# h2.net
KiCad netlist of a schematic drawn in EAGLE
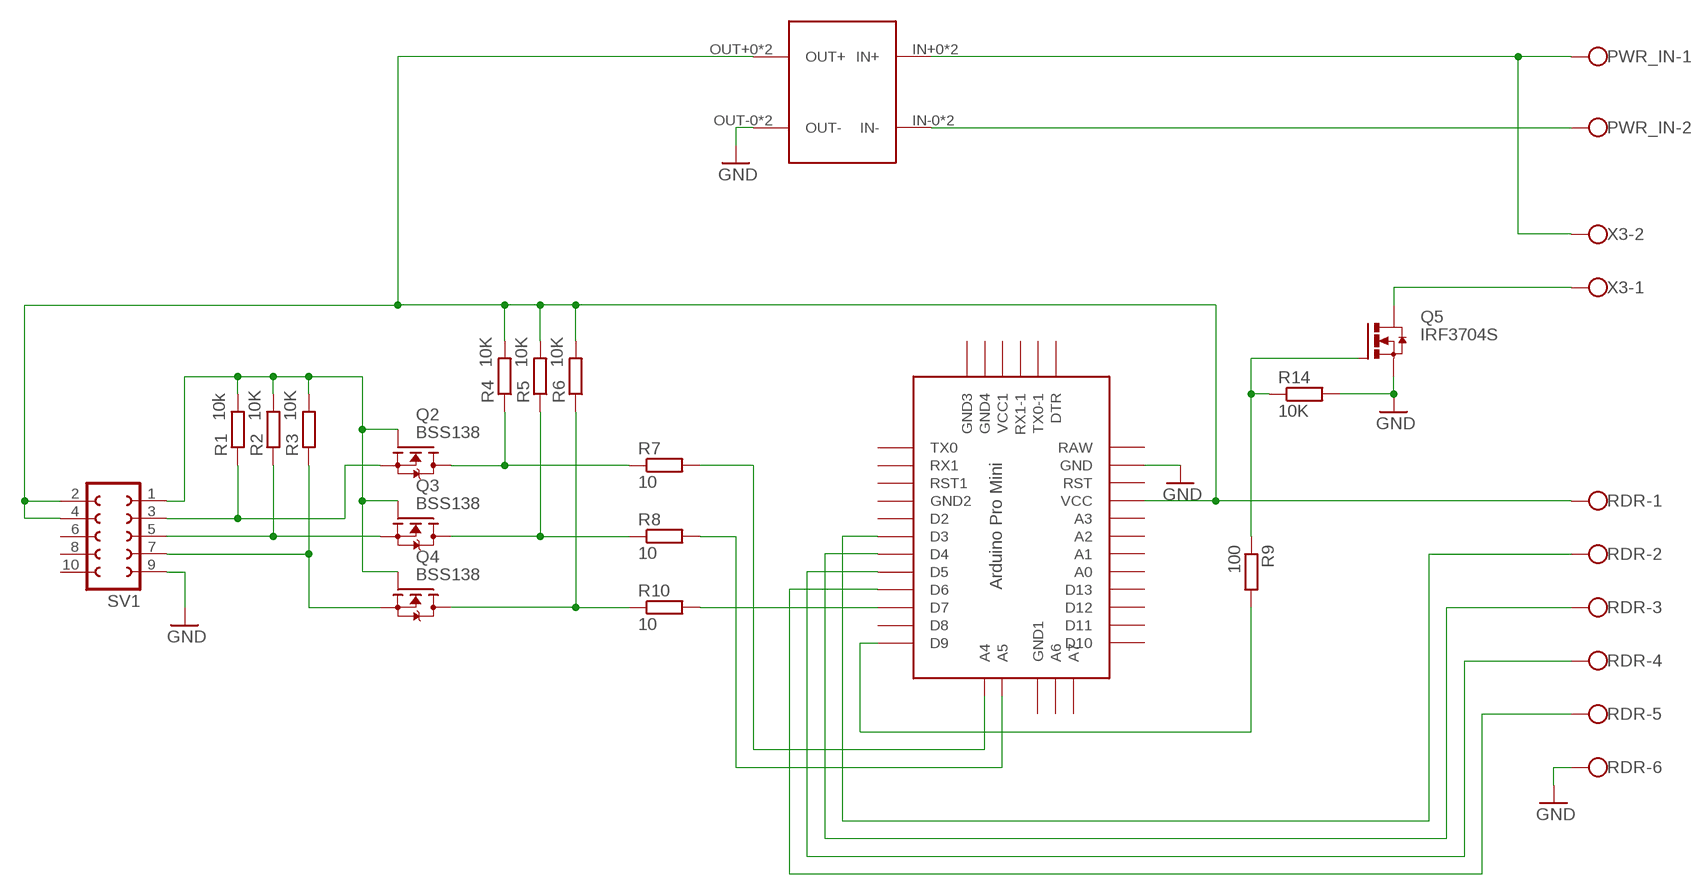
[diagram p0: schematic, sheet 1]

(export (version "E")
  (design (tool "Eeschema 10.0.6"))
  (components
    (comp (ref "PWR_IN")
      (value "W237-102")
      (footprint "eagle-import:W237-102")
      (fields (field (name "MPN") "237-102"))
      (libsource (lib "eagle-import") (part "W237-102"))
    )
    (comp (ref "Q2")
      (value "BSS138")
      (footprint "eagle-import:SOT23")
      (fields (field (name "MF") "Fairchild"))
      (libsource (lib "eagle-import") (part "BSS138"))
    )
    (comp (ref "Q3")
      (value "BSS138")
      (footprint "eagle-import:SOT23")
      (fields (field (name "MF") "Fairchild"))
      (libsource (lib "eagle-import") (part "BSS138"))
    )
    (comp (ref "Q4")
      (value "BSS138")
      (footprint "eagle-import:SOT23")
      (fields (field (name "MF") "Fairchild"))
      (libsource (lib "eagle-import") (part "BSS138"))
    )
    (comp (ref "Q5")
      (value "IRF3704S")
      (footprint "eagle-import:D2PACK")
      (libsource (lib "eagle-import") (part "IRF3704S"))
    )
    (comp (ref "R1")
      (value "10k")
      (footprint "eagle-import:R1206")
      (libsource (lib "eagle-import") (part "R-EU_R1206"))
    )
    (comp (ref "R2")
      (value "10K")
      (footprint "eagle-import:R1206")
      (libsource (lib "eagle-import") (part "R-EU_R1206"))
    )
    (comp (ref "R3")
      (value "10K")
      (footprint "eagle-import:R1206")
      (libsource (lib "eagle-import") (part "R-EU_R1206"))
    )
    (comp (ref "R4")
      (value "10K")
      (footprint "eagle-import:R1206")
      (libsource (lib "eagle-import") (part "R-EU_R1206"))
    )
    (comp (ref "R5")
      (value "10K")
      (footprint "eagle-import:R1206")
      (libsource (lib "eagle-import") (part "R-EU_R1206"))
    )
    (comp (ref "R6")
      (value "10K")
      (footprint "eagle-import:R1206")
      (libsource (lib "eagle-import") (part "R-EU_R1206"))
    )
    (comp (ref "R7")
      (value "10")
      (footprint "eagle-import:R1206")
      (libsource (lib "eagle-import") (part "R-EU_R1206"))
    )
    (comp (ref "R8")
      (value "10")
      (footprint "eagle-import:R1206")
      (libsource (lib "eagle-import") (part "R-EU_R1206"))
    )
    (comp (ref "R9")
      (value "100")
      (footprint "eagle-import:R1206")
      (libsource (lib "eagle-import") (part "R-EU_R1206"))
    )
    (comp (ref "R10")
      (value "10")
      (footprint "eagle-import:R1206")
      (libsource (lib "eagle-import") (part "R-EU_R1206"))
    )
    (comp (ref "R14")
      (value "10K")
      (footprint "eagle-import:R1206")
      (libsource (lib "eagle-import") (part "R-EU_R1206"))
    )
    (comp (ref "RDR")
      (value "W237-136")
      (footprint "eagle-import:W237-136")
      (fields (field (name "MPN") "237-136"))
      (libsource (lib "eagle-import") (part "W237-136"))
    )
    (comp (ref "SV1")
      (value "FE05-2")
      (footprint "eagle-import:FE05-2")
      (libsource (lib "eagle-import") (part "FE05-2"))
    )
    (comp (ref "U$1")
      (value "DC/DC4.5-20-ADJ")
      (footprint "eagle-import:23X17_8P")
      (libsource (lib "eagle-import") (part "DC/DC4.5-20-ADJ"))
    )
    (comp (ref "U$4")
      (value "ABK-PRO-MINI")
      (footprint "eagle-import:ABK-PRO-MINI")
      (libsource (lib "eagle-import") (part "ABK-PRO-MINI"))
    )
    (comp (ref "X3")
      (value "W237-102")
      (footprint "eagle-import:W237-102")
      (fields (field (name "MPN") "237-102"))
      (libsource (lib "eagle-import") (part "W237-102"))
    )
  )
  (nets
    (net (code "1") (name "GND") (class "Default")
      (node (ref "Q5") (pin "3") (pinfunction "S_3") (pintype "passive"))
      (node (ref "R14") (pin "2") (pinfunction "2_2") (pintype "passive"))
      (node (ref "RDR") (pin "6") (pinfunction "KL_6") (pintype "passive"))
      (node (ref "SV1") (pin "9") (pinfunction "9_9") (pintype "passive"))
      (node (ref "U$1") (pin "OUT-0") (pinfunction "OUT-_OUT-0") (pintype "bidirectional"))
      (node (ref "U$1") (pin "OUT-1") (pinfunction "OUT-_OUT-1") (pintype "bidirectional"))
      (node (ref "U$4") (pin "GND") (pinfunction "GND_GND") (pintype "bidirectional"))
    )
    (net (code "2") (name "Net-(PWR_INA-KL)") (class "Default")
      (node (ref "PWR_IN") (pin "1") (pinfunction "KL_1") (pintype "passive"))
      (node (ref "U$1") (pin "IN+0") (pinfunction "IN+_IN+0") (pintype "bidirectional"))
      (node (ref "U$1") (pin "IN+1") (pinfunction "IN+_IN+1") (pintype "bidirectional"))
      (node (ref "X3") (pin "2") (pinfunction "KL_2") (pintype "passive"))
    )
    (net (code "3") (name "Net-(PWR_INB-KL)") (class "Default")
      (node (ref "PWR_IN") (pin "2") (pinfunction "KL_2") (pintype "passive"))
      (node (ref "U$1") (pin "IN-0") (pinfunction "IN-_IN-0") (pintype "bidirectional"))
      (node (ref "U$1") (pin "IN-1") (pinfunction "IN-_IN-1") (pintype "bidirectional"))
    )
    (net (code "4") (name "Net-(Q2-D)") (class "Default")
      (node (ref "Q2") (pin "3") (pinfunction "D_3") (pintype "passive"))
      (node (ref "R4") (pin "1") (pinfunction "1_1") (pintype "passive"))
      (node (ref "R7") (pin "1") (pinfunction "1_1") (pintype "passive"))
    )
    (net (code "5") (name "Net-(Q2-G)") (class "Default")
      (node (ref "Q2") (pin "1") (pinfunction "G_1") (pintype "passive"))
      (node (ref "Q3") (pin "1") (pinfunction "G_1") (pintype "passive"))
      (node (ref "Q4") (pin "1") (pinfunction "G_1") (pintype "passive"))
      (node (ref "R1") (pin "2") (pinfunction "2_2") (pintype "passive"))
      (node (ref "R2") (pin "2") (pinfunction "2_2") (pintype "passive"))
      (node (ref "R3") (pin "2") (pinfunction "2_2") (pintype "passive"))
      (node (ref "SV1") (pin "1") (pinfunction "1_1") (pintype "passive"))
    )
    (net (code "6") (name "Net-(Q2-S)") (class "Default")
      (node (ref "Q2") (pin "2") (pinfunction "S_2") (pintype "passive"))
      (node (ref "R1") (pin "1") (pinfunction "1_1") (pintype "passive"))
      (node (ref "SV1") (pin "3") (pinfunction "3_3") (pintype "passive"))
    )
    (net (code "7") (name "Net-(Q3-D)") (class "Default")
      (node (ref "Q3") (pin "3") (pinfunction "D_3") (pintype "passive"))
      (node (ref "R5") (pin "1") (pinfunction "1_1") (pintype "passive"))
      (node (ref "R8") (pin "1") (pinfunction "1_1") (pintype "passive"))
    )
    (net (code "8") (name "Net-(Q3-S)") (class "Default")
      (node (ref "Q3") (pin "2") (pinfunction "S_2") (pintype "passive"))
      (node (ref "R2") (pin "1") (pinfunction "1_1") (pintype "passive"))
      (node (ref "SV1") (pin "5") (pinfunction "5_5") (pintype "passive"))
    )
    (net (code "9") (name "Net-(Q4-D)") (class "Default")
      (node (ref "Q4") (pin "3") (pinfunction "D_3") (pintype "passive"))
      (node (ref "R10") (pin "1") (pinfunction "1_1") (pintype "passive"))
      (node (ref "R6") (pin "1") (pinfunction "1_1") (pintype "passive"))
    )
    (net (code "10") (name "Net-(Q4-S)") (class "Default")
      (node (ref "Q4") (pin "2") (pinfunction "S_2") (pintype "passive"))
      (node (ref "R3") (pin "1") (pinfunction "1_1") (pintype "passive"))
      (node (ref "SV1") (pin "7") (pinfunction "7_7") (pintype "passive"))
    )
    (net (code "11") (name "Net-(Q5-D)") (class "Default")
      (node (ref "Q5") (pin "2") (pinfunction "D_2") (pintype "passive"))
      (node (ref "X3") (pin "1") (pinfunction "KL_1") (pintype "passive"))
    )
    (net (code "12") (name "Net-(Q5-G)") (class "Default")
      (node (ref "Q5") (pin "1") (pinfunction "G_1") (pintype "passive"))
      (node (ref "R14") (pin "1") (pinfunction "1_1") (pintype "passive"))
      (node (ref "R9") (pin "1") (pinfunction "1_1") (pintype "passive"))
    )
    (net (code "13") (name "Net-(R7-Pad2)") (class "Default")
      (node (ref "R7") (pin "2") (pinfunction "2_2") (pintype "passive"))
      (node (ref "U$4") (pin "A4") (pinfunction "A4_A4") (pintype "bidirectional"))
    )
    (net (code "14") (name "Net-(R8-Pad2)") (class "Default")
      (node (ref "R8") (pin "2") (pinfunction "2_2") (pintype "passive"))
      (node (ref "U$4") (pin "A5") (pinfunction "A5_A5") (pintype "bidirectional"))
    )
    (net (code "15") (name "Net-(R9-Pad2)") (class "Default")
      (node (ref "R9") (pin "2") (pinfunction "2_2") (pintype "passive"))
      (node (ref "U$4") (pin "D9") (pinfunction "D9_D9") (pintype "bidirectional"))
    )
    (net (code "16") (name "Net-(R10-Pad2)") (class "Default")
      (node (ref "R10") (pin "2") (pinfunction "2_2") (pintype "passive"))
      (node (ref "U$4") (pin "D7") (pinfunction "D7_D7") (pintype "bidirectional"))
    )
    (net (code "17") (name "Net-(RDRA-KL)") (class "Default")
      (node (ref "R4") (pin "2") (pinfunction "2_2") (pintype "passive"))
      (node (ref "R5") (pin "2") (pinfunction "2_2") (pintype "passive"))
      (node (ref "R6") (pin "2") (pinfunction "2_2") (pintype "passive"))
      (node (ref "RDR") (pin "1") (pinfunction "KL_1") (pintype "passive"))
      (node (ref "SV1") (pin "2") (pinfunction "2_2") (pintype "passive"))
      (node (ref "SV1") (pin "4") (pinfunction "4_4") (pintype "passive"))
      (node (ref "U$1") (pin "OUT+0") (pinfunction "OUT+_OUT+0") (pintype "bidirectional"))
      (node (ref "U$1") (pin "OUT+1") (pinfunction "OUT+_OUT+1") (pintype "bidirectional"))
      (node (ref "U$4") (pin "VCC") (pinfunction "VCC_VCC") (pintype "bidirectional"))
    )
    (net (code "18") (name "Net-(RDRB-KL)") (class "Default")
      (node (ref "RDR") (pin "2") (pinfunction "KL_2") (pintype "passive"))
      (node (ref "U$4") (pin "D3") (pinfunction "D3_D3") (pintype "bidirectional"))
    )
    (net (code "19") (name "Net-(RDRC-KL)") (class "Default")
      (node (ref "RDR") (pin "3") (pinfunction "KL_3") (pintype "passive"))
      (node (ref "U$4") (pin "D4") (pinfunction "D4_D4") (pintype "bidirectional"))
    )
    (net (code "20") (name "Net-(RDRD-KL)") (class "Default")
      (node (ref "RDR") (pin "4") (pinfunction "KL_4") (pintype "passive"))
      (node (ref "U$4") (pin "D5") (pinfunction "D5_D5") (pintype "bidirectional"))
    )
    (net (code "21") (name "Net-(RDRE-KL)") (class "Default")
      (node (ref "RDR") (pin "5") (pinfunction "KL_5") (pintype "passive"))
      (node (ref "U$4") (pin "D6") (pinfunction "D6_D6") (pintype "bidirectional"))
    )
    (net (code "22") (name "unconnected-(SV1-Pad6)") (class "Default")
      (node (ref "SV1") (pin "6") (pinfunction "6_6") (pintype "passive"))
    )
    (net (code "23") (name "unconnected-(SV1-Pad8)") (class "Default")
      (node (ref "SV1") (pin "8") (pinfunction "8_8") (pintype "passive"))
    )
    (net (code "24") (name "unconnected-(SV1-Pad10)") (class "Default")
      (node (ref "SV1") (pin "10") (pinfunction "10_10") (pintype "passive"))
    )
    (net (code "25") (name "unconnected-(U$4-GND1-PadGND4)") (class "Default")
      (node (ref "U$4") (pin "GND4") (pinfunction "GND1_GND4") (pintype "bidirectional"))
    )
    (net (code "26") (name "unconnected-(U$4-GND2-PadGND1)") (class "Default")
      (node (ref "U$4") (pin "GND1") (pinfunction "GND2_GND1") (pintype "bidirectional"))
    )
    (net (code "27") (name "unconnected-(U$4-GND3-PadGND2)") (class "Default")
      (node (ref "U$4") (pin "GND2") (pinfunction "GND3_GND2") (pintype "bidirectional"))
    )
    (net (code "28") (name "unconnected-(U$4-GND4-PadGND3)") (class "Default")
      (node (ref "U$4") (pin "GND3") (pinfunction "GND4_GND3") (pintype "bidirectional"))
    )
    (net (code "29") (name "unconnected-(U$4-PadA0)") (class "Default")
      (node (ref "U$4") (pin "A0") (pinfunction "A0_A0") (pintype "bidirectional"))
    )
    (net (code "30") (name "unconnected-(U$4-PadA1)") (class "Default")
      (node (ref "U$4") (pin "A1") (pinfunction "A1_A1") (pintype "bidirectional"))
    )
    (net (code "31") (name "unconnected-(U$4-PadA2)") (class "Default")
      (node (ref "U$4") (pin "A2") (pinfunction "A2_A2") (pintype "bidirectional"))
    )
    (net (code "32") (name "unconnected-(U$4-PadA3)") (class "Default")
      (node (ref "U$4") (pin "A3") (pinfunction "A3_A3") (pintype "bidirectional"))
    )
    (net (code "33") (name "unconnected-(U$4-PadA6)") (class "Default")
      (node (ref "U$4") (pin "A6") (pinfunction "A6_A6") (pintype "bidirectional"))
    )
    (net (code "34") (name "unconnected-(U$4-PadA7)") (class "Default")
      (node (ref "U$4") (pin "A7") (pinfunction "A7_A7") (pintype "bidirectional"))
    )
    (net (code "35") (name "unconnected-(U$4-PadD2)") (class "Default")
      (node (ref "U$4") (pin "D2") (pinfunction "D2_D2") (pintype "bidirectional"))
    )
    (net (code "36") (name "unconnected-(U$4-PadD8)") (class "Default")
      (node (ref "U$4") (pin "D8") (pinfunction "D8_D8") (pintype "bidirectional"))
    )
    (net (code "37") (name "unconnected-(U$4-PadD10)") (class "Default")
      (node (ref "U$4") (pin "D10") (pinfunction "D10_D10") (pintype "bidirectional"))
    )
    (net (code "38") (name "unconnected-(U$4-PadD11)") (class "Default")
      (node (ref "U$4") (pin "D11") (pinfunction "D11_D11") (pintype "bidirectional"))
    )
    (net (code "39") (name "unconnected-(U$4-PadD12)") (class "Default")
      (node (ref "U$4") (pin "D12") (pinfunction "D12_D12") (pintype "bidirectional"))
    )
    (net (code "40") (name "unconnected-(U$4-PadD13)") (class "Default")
      (node (ref "U$4") (pin "D13") (pinfunction "D13_D13") (pintype "bidirectional"))
    )
    (net (code "41") (name "unconnected-(U$4-PadDTR)") (class "Default")
      (node (ref "U$4") (pin "DTR") (pinfunction "DTR_DTR") (pintype "bidirectional"))
    )
    (net (code "42") (name "unconnected-(U$4-PadRAW)") (class "Default")
      (node (ref "U$4") (pin "RAW") (pinfunction "RAW_RAW") (pintype "bidirectional"))
    )
    (net (code "43") (name "unconnected-(U$4-PadRST)") (class "Default")
      (node (ref "U$4") (pin "RST") (pinfunction "RST_RST") (pintype "bidirectional"))
    )
    (net (code "44") (name "unconnected-(U$4-PadRST1)") (class "Default")
      (node (ref "U$4") (pin "RST1") (pinfunction "RST1_RST1") (pintype "bidirectional"))
    )
    (net (code "45") (name "unconnected-(U$4-PadRX1)") (class "Default")
      (node (ref "U$4") (pin "RX1") (pinfunction "RX1_RX1") (pintype "bidirectional"))
    )
    (net (code "46") (name "unconnected-(U$4-PadRX1-1)") (class "Default")
      (node (ref "U$4") (pin "RX1-1") (pinfunction "RX1-1_RX1-1") (pintype "bidirectional"))
    )
    (net (code "47") (name "unconnected-(U$4-PadTX0)") (class "Default")
      (node (ref "U$4") (pin "TX0") (pinfunction "TX0_TX0") (pintype "bidirectional"))
    )
    (net (code "48") (name "unconnected-(U$4-PadTX0-1)") (class "Default")
      (node (ref "U$4") (pin "TX0-1") (pinfunction "TX0-1_TX0-1") (pintype "bidirectional"))
    )
    (net (code "49") (name "unconnected-(U$4-PadVCC1)") (class "Default")
      (node (ref "U$4") (pin "VCC1") (pinfunction "VCC1_VCC1") (pintype "bidirectional"))
    )
  )
)
